# DS12c887.net
KiCad netlist of a schematic drawn in Altium Designer
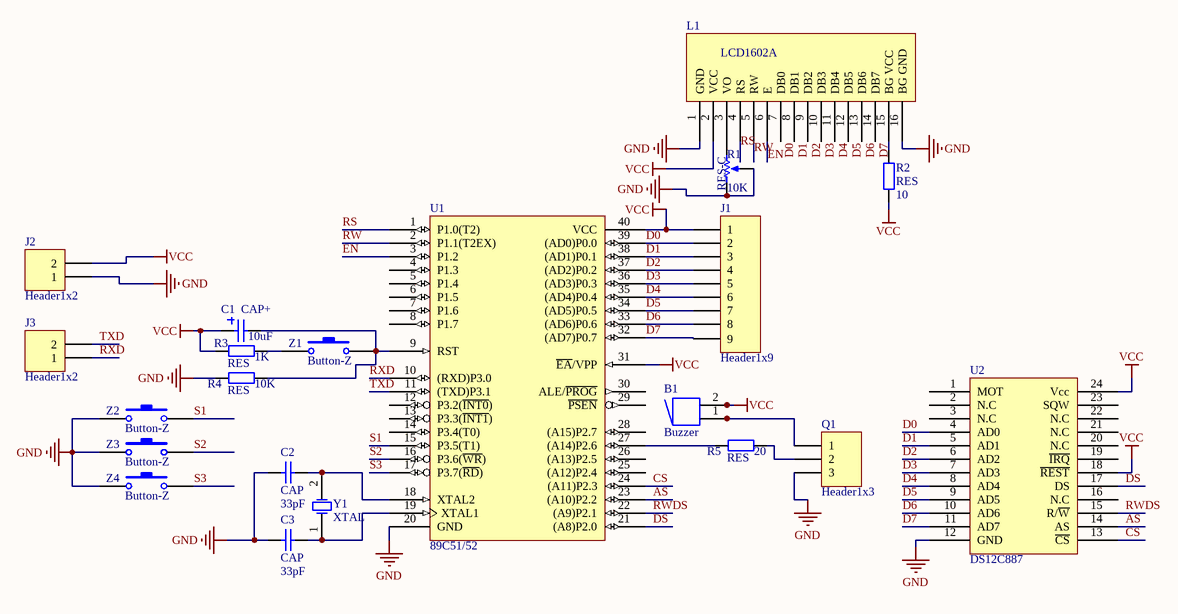
[diagram p0: DS12c887.SchDoc]

(export (version "E")
  (design (tool "Eeschema 10.0.6"))
  (components
    (comp (ref "B1") (value "Buzzer") (footprint "BUZZER") (libsource (lib "ZYF_Common") (part "Buzzer")))
    (comp (ref "C1")
      (value "CAP+")
      (footprint "CAP+DIP")
      (fields (field (name "ALTIUM_UNNAMED_1") "10uF"))
      (libsource (lib "ZYF_Common") (part "CAP+DIP"))
    )
    (comp (ref "C2")
      (value "CAP")
      (footprint "CAP")
      (fields (field (name "ALTIUM_UNNAMED_1") "33pF"))
      (libsource (lib "ZYF_Common") (part "CAP"))
    )
    (comp (ref "C3")
      (value "CAP")
      (footprint "CAP")
      (fields (field (name "ALTIUM_UNNAMED_1") "33pF"))
      (libsource (lib "ZYF_Common") (part "CAP"))
    )
    (comp (ref "J1")
      (value "Header1x9")
      (footprint "HEADER1X9")
      (libsource (lib "ZYF_Connector") (part "Header1x9"))
    )
    (comp (ref "J2")
      (value "Header1x2")
      (footprint "HEADER1X2")
      (libsource (lib "ZYF_Connector") (part "Header1x2"))
    )
    (comp (ref "J3")
      (value "Header1x2")
      (footprint "HEADER1X2")
      (libsource (lib "ZYF_Connector") (part "Header1x2"))
    )
    (comp (ref "L1")
      (value "LCD1602A")
      (footprint "LCD1602A")
      (libsource (lib "ZYF_Common") (part "LCD1602A"))
    )
    (comp (ref "Q1")
      (value "Header1x3")
      (footprint "HEADER1X3")
      (libsource (lib "ZYF_Connector") (part "Header1x3"))
    )
    (comp (ref "R1")
      (value "RES-C")
      (footprint "RES-Change-T")
      (fields (field (name "ALTIUM_UNNAMED_1") "10K"))
      (libsource (lib "ZYF_Common") (part "RES-Change-T"))
    )
    (comp (ref "R2")
      (value "RES")
      (footprint "RES")
      (fields (field (name "ALTIUM_UNNAMED_1") "10"))
      (libsource (lib "ZYF_Common") (part "RES"))
    )
    (comp (ref "R3")
      (value "RES")
      (footprint "RES")
      (fields (field (name "ALTIUM_UNNAMED_1") "1K"))
      (libsource (lib "ZYF_Common") (part "RES"))
    )
    (comp (ref "R4")
      (value "RES")
      (footprint "RES")
      (fields (field (name "ALTIUM_UNNAMED_1") "10K"))
      (libsource (lib "ZYF_Common") (part "RES"))
    )
    (comp (ref "R5")
      (value "RES")
      (footprint "RES")
      (fields (field (name "ALTIUM_UNNAMED_1") "20"))
      (libsource (lib "ZYF_Common") (part "RES"))
    )
    (comp (ref "U1") (value "89C51/52") (footprint "DIP-40") (libsource (lib "ZYF_IC") (part "89C51/52")))
    (comp (ref "U2") (value "DS12C887") (footprint "DIP-24") (libsource (lib "ZYF_IC") (part "DS12C887")))
    (comp (ref "Y1") (value "XTAL") (footprint "XTAL") (libsource (lib "ZYF_Common") (part "XTAL")))
    (comp (ref "Z1")
      (value "Button-Z")
      (footprint "SW-PB-Z")
      (libsource (lib "ZYF_Common") (part "SW-Button-Z"))
    )
    (comp (ref "Z2")
      (value "Button-Z")
      (footprint "SW-PB-Z")
      (libsource (lib "ZYF_Common") (part "SW-Button-Z"))
    )
    (comp (ref "Z3")
      (value "Button-Z")
      (footprint "SW-PB-Z")
      (libsource (lib "ZYF_Common") (part "SW-Button-Z"))
    )
    (comp (ref "Z4")
      (value "Button-Z")
      (footprint "SW-PB-Z")
      (libsource (lib "ZYF_Common") (part "SW-Button-Z"))
    )
  )
  (nets
    (net (code "1") (name "/AS") (class "Default")
      (node (ref "U1") (pin "23") (pinfunction "(A10)P2.2_23") (pintype "bidirectional"))
      (node (ref "U2") (pin "14") (pinfunction "AS_14") (pintype "passive"))
    )
    (net (code "2") (name "/CS") (class "Default")
      (node (ref "U1") (pin "24") (pinfunction "(A11)P2.3_24") (pintype "bidirectional"))
      (node (ref "U2") (pin "13") (pinfunction "~{CS}_13") (pintype "passive"))
    )
    (net (code "3") (name "/D0") (class "Default")
      (node (ref "J1") (pin "2") (pinfunction "2_2") (pintype "passive"))
      (node (ref "L1") (pin "7") (pinfunction "DB0_7") (pintype "passive"))
      (node (ref "U1") (pin "39") (pinfunction "(AD0)P0.0_39") (pintype "bidirectional"))
      (node (ref "U2") (pin "4") (pinfunction "AD0_4") (pintype "passive"))
    )
    (net (code "4") (name "/D1") (class "Default")
      (node (ref "J1") (pin "3") (pinfunction "3_3") (pintype "passive"))
      (node (ref "L1") (pin "8") (pinfunction "DB1_8") (pintype "passive"))
      (node (ref "U1") (pin "38") (pinfunction "(AD1)P0.1_38") (pintype "bidirectional"))
      (node (ref "U2") (pin "5") (pinfunction "AD1_5") (pintype "passive"))
    )
    (net (code "5") (name "/D2") (class "Default")
      (node (ref "J1") (pin "4") (pinfunction "4_4") (pintype "passive"))
      (node (ref "L1") (pin "9") (pinfunction "DB2_9") (pintype "passive"))
      (node (ref "U1") (pin "37") (pinfunction "(AD2)P0.2_37") (pintype "bidirectional"))
      (node (ref "U2") (pin "6") (pinfunction "AD2_6") (pintype "passive"))
    )
    (net (code "6") (name "/D3") (class "Default")
      (node (ref "J1") (pin "5") (pinfunction "5_5") (pintype "passive"))
      (node (ref "L1") (pin "10") (pinfunction "DB3_10") (pintype "passive"))
      (node (ref "U1") (pin "36") (pinfunction "(AD3)P0.3_36") (pintype "bidirectional"))
      (node (ref "U2") (pin "7") (pinfunction "AD3_7") (pintype "passive"))
    )
    (net (code "7") (name "/D4") (class "Default")
      (node (ref "J1") (pin "6") (pinfunction "6_6") (pintype "passive"))
      (node (ref "L1") (pin "11") (pinfunction "DB4_11") (pintype "passive"))
      (node (ref "U1") (pin "35") (pinfunction "(AD4)P0.4_35") (pintype "bidirectional"))
      (node (ref "U2") (pin "8") (pinfunction "AD4_8") (pintype "passive"))
    )
    (net (code "8") (name "/D5") (class "Default")
      (node (ref "J1") (pin "7") (pinfunction "7_7") (pintype "passive"))
      (node (ref "L1") (pin "12") (pinfunction "DB5_12") (pintype "passive"))
      (node (ref "U1") (pin "34") (pinfunction "(AD5)P0.5_34") (pintype "bidirectional"))
      (node (ref "U2") (pin "9") (pinfunction "AD5_9") (pintype "passive"))
    )
    (net (code "9") (name "/D6") (class "Default")
      (node (ref "J1") (pin "8") (pinfunction "8_8") (pintype "passive"))
      (node (ref "L1") (pin "13") (pinfunction "DB6_13") (pintype "passive"))
      (node (ref "U1") (pin "33") (pinfunction "(AD6)P0.6_33") (pintype "bidirectional"))
      (node (ref "U2") (pin "10") (pinfunction "AD6_10") (pintype "passive"))
    )
    (net (code "10") (name "/D7") (class "Default")
      (node (ref "J1") (pin "9") (pinfunction "9_9") (pintype "passive"))
      (node (ref "L1") (pin "14") (pinfunction "DB7_14") (pintype "passive"))
      (node (ref "U1") (pin "32") (pinfunction "(AD7)P0.7_32") (pintype "bidirectional"))
      (node (ref "U2") (pin "11") (pinfunction "AD7_11") (pintype "passive"))
    )
    (net (code "11") (name "/DS") (class "Default")
      (node (ref "U1") (pin "21") (pinfunction "(A8)P2.0_21") (pintype "bidirectional"))
      (node (ref "U2") (pin "17") (pinfunction "DS_17") (pintype "passive"))
    )
    (net (code "12") (name "/EN") (class "Default")
      (node (ref "L1") (pin "6") (pinfunction "E_6") (pintype "passive"))
      (node (ref "U1") (pin "3") (pinfunction "P1.2_3") (pintype "bidirectional"))
    )
    (net (code "13") (name "/RS") (class "Default")
      (node (ref "L1") (pin "4") (pinfunction "RS_4") (pintype "passive"))
      (node (ref "U1") (pin "1") (pinfunction "P1.0(T2)_1") (pintype "bidirectional"))
    )
    (net (code "14") (name "/RW") (class "Default")
      (node (ref "L1") (pin "5") (pinfunction "RW_5") (pintype "passive"))
      (node (ref "U1") (pin "2") (pinfunction "P1.1(T2EX)_2") (pintype "bidirectional"))
    )
    (net (code "15") (name "/RWDS") (class "Default")
      (node (ref "U1") (pin "22") (pinfunction "(A9)P2.1_22") (pintype "bidirectional"))
      (node (ref "U2") (pin "15") (pinfunction "R/~{W}_15") (pintype "passive"))
    )
    (net (code "16") (name "/RXD") (class "Default")
      (node (ref "J3") (pin "1") (pinfunction "1_1") (pintype "passive"))
      (node (ref "U1") (pin "10") (pinfunction "(RXD)P3.0_10") (pintype "bidirectional"))
    )
    (net (code "17") (name "/S1") (class "Default")
      (node (ref "U1") (pin "15") (pinfunction "P3.5(T1)_15") (pintype "bidirectional"))
      (node (ref "Z2") (pin "2") (pinfunction "2_2") (pintype "passive"))
    )
    (net (code "18") (name "/S2") (class "Default")
      (node (ref "U1") (pin "16") (pinfunction "P3.6(~{WR})_16") (pintype "bidirectional"))
      (node (ref "Z3") (pin "2") (pinfunction "2_2") (pintype "passive"))
    )
    (net (code "19") (name "/S3") (class "Default")
      (node (ref "U1") (pin "17") (pinfunction "P3.7(~{RD})_17") (pintype "bidirectional"))
      (node (ref "Z4") (pin "2") (pinfunction "2_2") (pintype "passive"))
    )
    (net (code "20") (name "/TXD") (class "Default")
      (node (ref "J3") (pin "2") (pinfunction "2_2") (pintype "passive"))
      (node (ref "U1") (pin "11") (pinfunction "(TXD)P3.1_11") (pintype "bidirectional"))
    )
    (net (code "21") (name "GND") (class "Default")
      (node (ref "C2") (pin "2") (pinfunction "2_2") (pintype "passive"))
      (node (ref "C3") (pin "2") (pinfunction "2_2") (pintype "passive"))
      (node (ref "J2") (pin "1") (pinfunction "1_1") (pintype "passive"))
      (node (ref "L1") (pin "1") (pinfunction "GND_1") (pintype "passive"))
      (node (ref "L1") (pin "16") (pinfunction "BG_GND_16") (pintype "passive"))
      (node (ref "Q1") (pin "3") (pinfunction "3_3") (pintype "passive"))
      (node (ref "R1") (pin "1") (pinfunction "TOP_1") (pintype "passive"))
      (node (ref "R1") (pin "3") (pinfunction "TAP_3") (pintype "passive"))
      (node (ref "R4") (pin "1") (pinfunction "1_1") (pintype "passive"))
      (node (ref "U1") (pin "20") (pinfunction "GND_20") (pintype "power_in"))
      (node (ref "U2") (pin "12") (pinfunction "GND_12") (pintype "passive"))
      (node (ref "Z2") (pin "1") (pinfunction "1_1") (pintype "passive"))
      (node (ref "Z3") (pin "1") (pinfunction "1_1") (pintype "passive"))
      (node (ref "Z4") (pin "1") (pinfunction "1_1") (pintype "passive"))
    )
    (net (code "22") (name "Net-(B1-Pad1)") (class "Default")
      (node (ref "B1") (pin "1") (pinfunction "1_1") (pintype "passive"))
      (node (ref "Q1") (pin "1") (pinfunction "1_1") (pintype "passive"))
    )
    (net (code "23") (name "Net-(L1-BG_VCC)") (class "Default")
      (node (ref "L1") (pin "15") (pinfunction "BG_VCC_15") (pintype "passive"))
      (node (ref "R2") (pin "2") (pinfunction "2_2") (pintype "passive"))
    )
    (net (code "24") (name "Net-(L1-VO)") (class "Default")
      (node (ref "L1") (pin "3") (pinfunction "VO_3") (pintype "passive"))
      (node (ref "R1") (pin "2") (pinfunction "BOT_2") (pintype "passive"))
    )
    (net (code "25") (name "Net-(Q1-Pad2)") (class "Default")
      (node (ref "Q1") (pin "2") (pinfunction "2_2") (pintype "passive"))
      (node (ref "R5") (pin "2") (pinfunction "2_2") (pintype "passive"))
    )
    (net (code "26") (name "Net-(R3-Pad1)") (class "Default")
      (node (ref "R3") (pin "1") (pinfunction "1_1") (pintype "passive"))
      (node (ref "Z1") (pin "1") (pinfunction "1_1") (pintype "passive"))
    )
    (net (code "27") (name "Net-(U1-(A14)P2.6)") (class "Default")
      (node (ref "R5") (pin "1") (pinfunction "1_1") (pintype "passive"))
      (node (ref "U1") (pin "27") (pinfunction "(A14)P2.6_27") (pintype "bidirectional"))
    )
    (net (code "28") (name "Net-(U1-RST)") (class "Default")
      (node (ref "C1") (pin "2") (pinfunction "2_2") (pintype "passive"))
      (node (ref "R4") (pin "2") (pinfunction "2_2") (pintype "passive"))
      (node (ref "U1") (pin "9") (pinfunction "RST_9") (pintype "input"))
      (node (ref "Z1") (pin "2") (pinfunction "2_2") (pintype "passive"))
    )
    (net (code "29") (name "Net-(U1-XTAL1)") (class "Default")
      (node (ref "C3") (pin "1") (pinfunction "1_1") (pintype "passive"))
      (node (ref "U1") (pin "19") (pinfunction "XTAL1_19") (pintype "input"))
      (node (ref "Y1") (pin "1") (pinfunction "OSC1_1") (pintype "passive"))
    )
    (net (code "30") (name "Net-(U1-XTAL2)") (class "Default")
      (node (ref "C2") (pin "1") (pinfunction "1_1") (pintype "passive"))
      (node (ref "U1") (pin "18") (pinfunction "XTAL2_18") (pintype "input"))
      (node (ref "Y1") (pin "2") (pinfunction "OSC2_2") (pintype "passive"))
    )
    (net (code "31") (name "VCC") (class "Default")
      (node (ref "B1") (pin "2") (pinfunction "2_2") (pintype "passive"))
      (node (ref "C1") (pin "1") (pinfunction "1_1") (pintype "passive"))
      (node (ref "J1") (pin "1") (pinfunction "1_1") (pintype "passive"))
      (node (ref "J2") (pin "2") (pinfunction "2_2") (pintype "passive"))
      (node (ref "L1") (pin "2") (pinfunction "VCC_2") (pintype "passive"))
      (node (ref "R2") (pin "1") (pinfunction "1_1") (pintype "passive"))
      (node (ref "R3") (pin "2") (pinfunction "2_2") (pintype "passive"))
      (node (ref "U1") (pin "31") (pinfunction "~{EA}/VPP_31") (pintype "input"))
      (node (ref "U1") (pin "40") (pinfunction "VCC_40") (pintype "power_in"))
      (node (ref "U2") (pin "18") (pinfunction "~{REST}_18") (pintype "passive"))
      (node (ref "U2") (pin "24") (pinfunction "Vcc_24") (pintype "passive"))
    )
    (net (code "32") (name "unconnected-(U1-(A12)P2.4-Pad25)") (class "Default")
      (node (ref "U1") (pin "25") (pinfunction "(A12)P2.4_25") (pintype "bidirectional"))
    )
    (net (code "33") (name "unconnected-(U1-(A13)P2.5-Pad26)") (class "Default")
      (node (ref "U1") (pin "26") (pinfunction "(A13)P2.5_26") (pintype "bidirectional"))
    )
    (net (code "34") (name "unconnected-(U1-(A15)P2.7-Pad28)") (class "Default")
      (node (ref "U1") (pin "28") (pinfunction "(A15)P2.7_28") (pintype "bidirectional"))
    )
    (net (code "35") (name "unconnected-(U1-ALE{slash}~{PROG}-Pad30)") (class "Default")
      (node (ref "U1") (pin "30") (pinfunction "ALE/~{PROG}_30") (pintype "output"))
    )
    (net (code "36") (name "unconnected-(U1-P1.3-Pad4)") (class "Default")
      (node (ref "U1") (pin "4") (pinfunction "P1.3_4") (pintype "bidirectional"))
    )
    (net (code "37") (name "unconnected-(U1-P1.4-Pad5)") (class "Default")
      (node (ref "U1") (pin "5") (pinfunction "P1.4_5") (pintype "bidirectional"))
    )
    (net (code "38") (name "unconnected-(U1-P1.5-Pad6)") (class "Default")
      (node (ref "U1") (pin "6") (pinfunction "P1.5_6") (pintype "bidirectional"))
    )
    (net (code "39") (name "unconnected-(U1-P1.6-Pad7)") (class "Default")
      (node (ref "U1") (pin "7") (pinfunction "P1.6_7") (pintype "bidirectional"))
    )
    (net (code "40") (name "unconnected-(U1-P1.7-Pad8)") (class "Default")
      (node (ref "U1") (pin "8") (pinfunction "P1.7_8") (pintype "bidirectional"))
    )
    (net (code "41") (name "unconnected-(U1-P3.2(~{INT0})-Pad12)") (class "Default")
      (node (ref "U1") (pin "12") (pinfunction "P3.2(~{INT0})_12") (pintype "bidirectional"))
    )
    (net (code "42") (name "unconnected-(U1-P3.3(~{INT1})-Pad13)") (class "Default")
      (node (ref "U1") (pin "13") (pinfunction "P3.3(~{INT1})_13") (pintype "bidirectional"))
    )
    (net (code "43") (name "unconnected-(U1-P3.4(T0)-Pad14)") (class "Default")
      (node (ref "U1") (pin "14") (pinfunction "P3.4(T0)_14") (pintype "bidirectional"))
    )
    (net (code "44") (name "unconnected-(U1-~{PSEN}-Pad29)") (class "Default")
      (node (ref "U1") (pin "29") (pinfunction "~{PSEN}_29") (pintype "output"))
    )
    (net (code "45") (name "unconnected-(U2-MOT-Pad1)") (class "Default")
      (node (ref "U2") (pin "1") (pinfunction "MOT_1") (pintype "passive"))
    )
    (net (code "46") (name "unconnected-(U2-N.C-Pad2)") (class "Default")
      (node (ref "U2") (pin "2") (pinfunction "N.C_2") (pintype "passive"))
    )
    (net (code "47") (name "unconnected-(U2-N.C-Pad3)") (class "Default")
      (node (ref "U2") (pin "3") (pinfunction "N.C_3") (pintype "passive"))
    )
    (net (code "48") (name "unconnected-(U2-N.C-Pad16)") (class "Default")
      (node (ref "U2") (pin "16") (pinfunction "N.C_16") (pintype "passive"))
    )
    (net (code "49") (name "unconnected-(U2-N.C-Pad20)") (class "Default")
      (node (ref "U2") (pin "20") (pinfunction "N.C_20") (pintype "passive"))
    )
    (net (code "50") (name "unconnected-(U2-N.C-Pad21)") (class "Default")
      (node (ref "U2") (pin "21") (pinfunction "N.C_21") (pintype "passive"))
    )
    (net (code "51") (name "unconnected-(U2-N.C-Pad22)") (class "Default")
      (node (ref "U2") (pin "22") (pinfunction "N.C_22") (pintype "passive"))
    )
    (net (code "52") (name "unconnected-(U2-SQW-Pad23)") (class "Default")
      (node (ref "U2") (pin "23") (pinfunction "SQW_23") (pintype "passive"))
    )
    (net (code "53") (name "unconnected-(U2-~{IRQ}-Pad19)") (class "Default")
      (node (ref "U2") (pin "19") (pinfunction "~{IRQ}_19") (pintype "passive"))
    )
  )
)
